# Adafruit_NeoPixel_JST_SH_Breakout.net
KiCad netlist of a schematic drawn in EAGLE
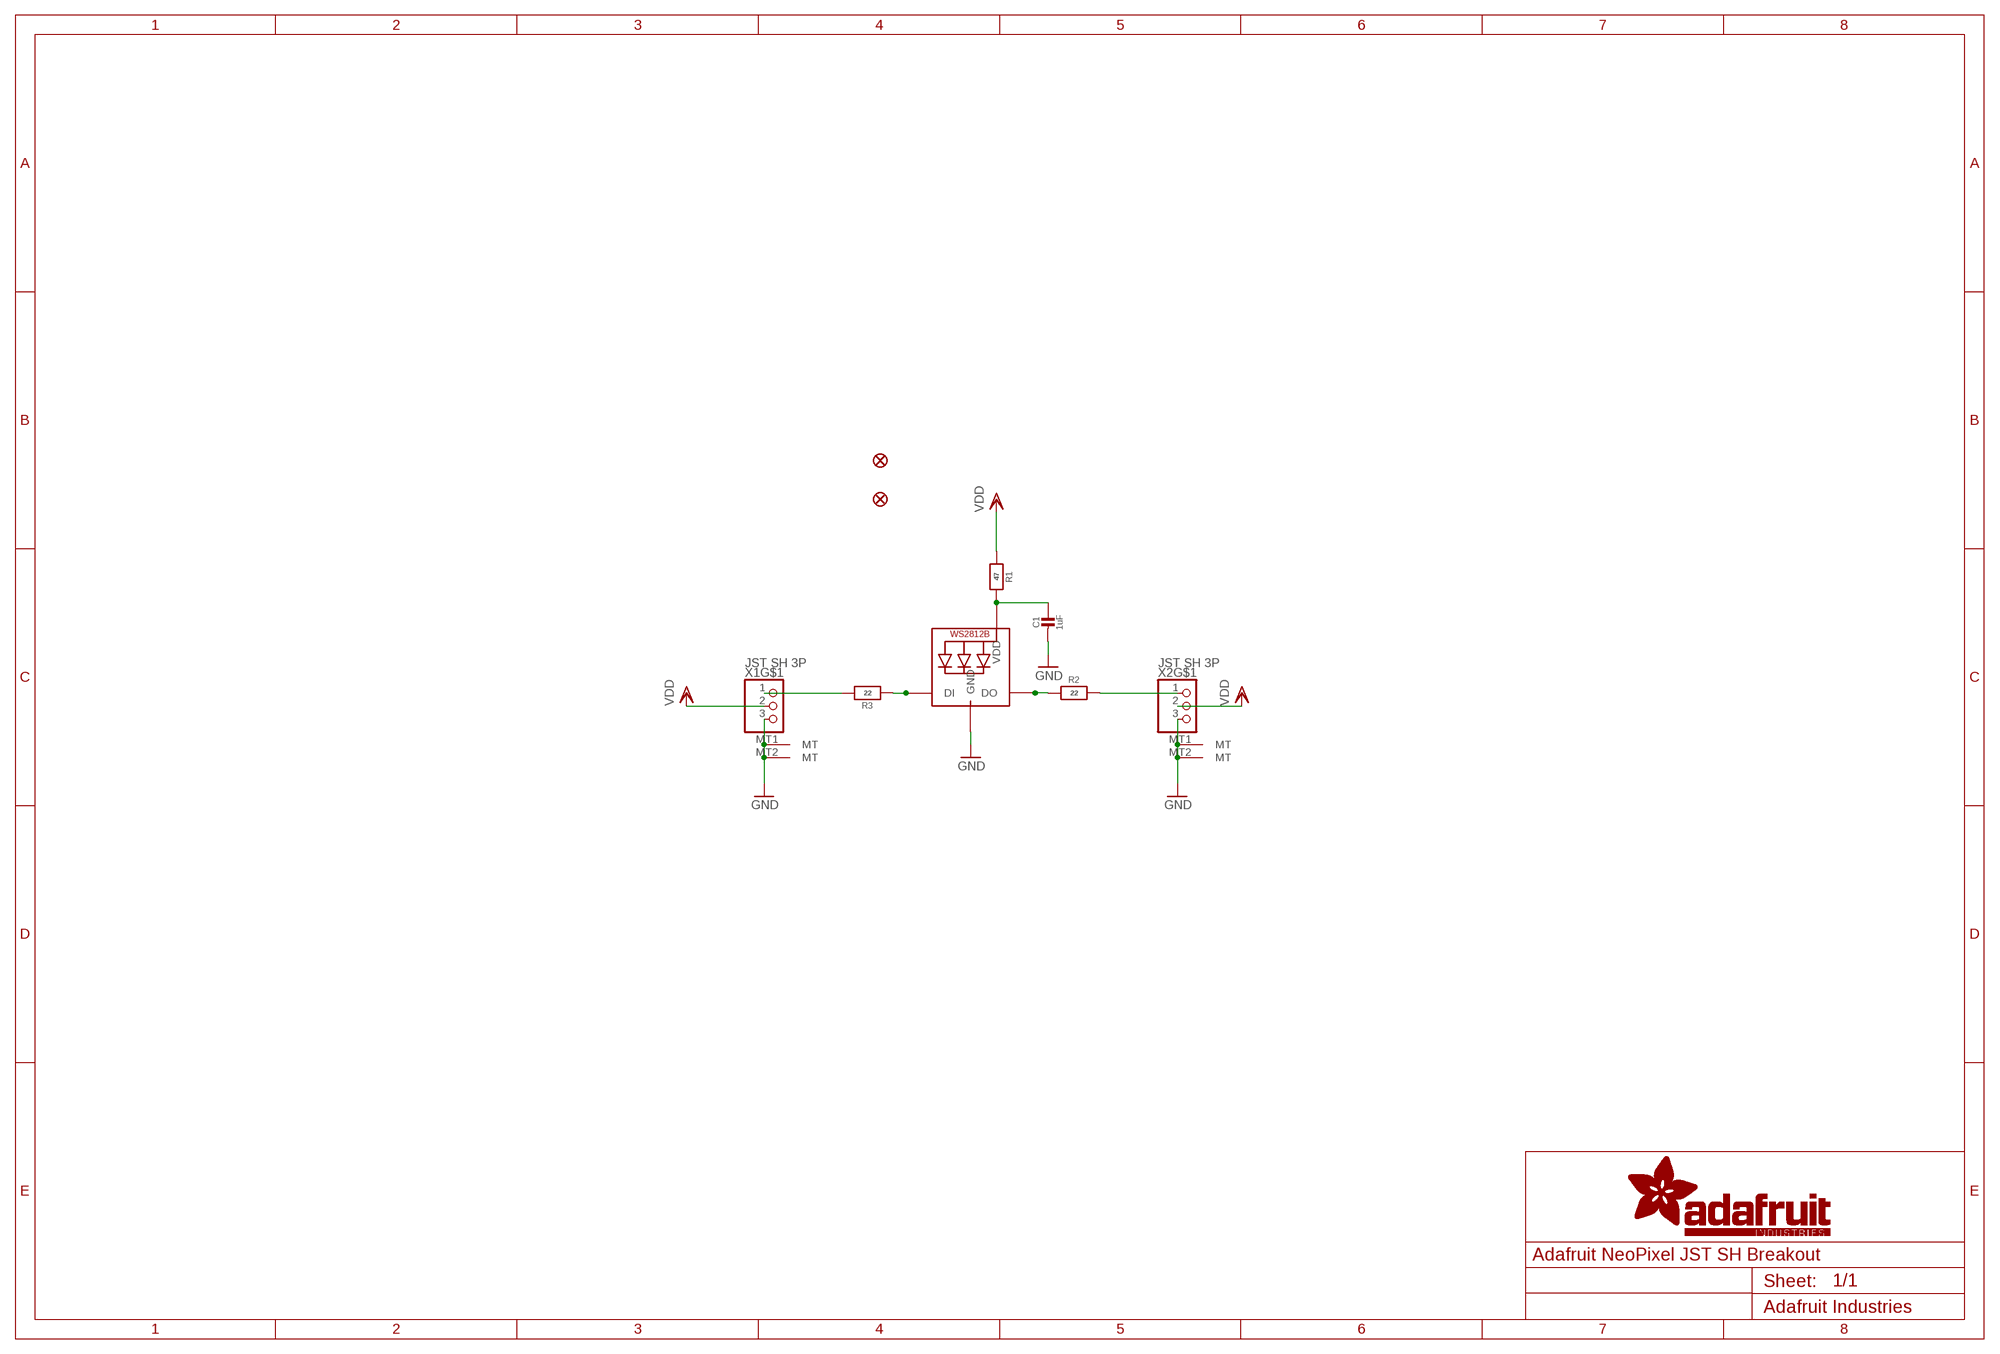
[diagram p0: schematic, sheet 1]

(export (version "E")
  (design (tool "Eeschema 10.0.6"))
  (components
    (comp (ref "C1")
      (value "1uF")
      (footprint "eagle-import:0603-NO")
      (libsource (lib "eagle-import") (part "CAP_CERAMIC0603_NO"))
    )
    (comp (ref "FID1")
      (value "FIDUCIAL_0.5MM")
      (footprint "eagle-import:FIDUCIAL_0.5MM")
      (libsource (lib "eagle-import") (part "FIDUCIAL_0.5MM"))
    )
    (comp (ref "FID2")
      (value "FIDUCIAL_0.5MM")
      (footprint "eagle-import:FIDUCIAL_0.5MM")
      (libsource (lib "eagle-import") (part "FIDUCIAL_0.5MM"))
    )
    (comp (ref "LED2")
      (value "WS2812B_5050N")
      (footprint "eagle-import:WS2812B-NARROW")
      (libsource (lib "eagle-import") (part "WS2812B_5050N"))
    )
    (comp (ref "R1")
      (value "47")
      (footprint "eagle-import:_0402NO")
      (libsource (lib "eagle-import") (part "RESISTOR_0402NO"))
    )
    (comp (ref "R2")
      (value "22")
      (footprint "eagle-import:_0402NO")
      (libsource (lib "eagle-import") (part "RESISTOR_0402NO"))
    )
    (comp (ref "R3")
      (value "22")
      (footprint "eagle-import:_0402NO")
      (libsource (lib "eagle-import") (part "RESISTOR_0402NO"))
    )
    (comp (ref "X1")
      (value "JST SH 3P")
      (footprint "eagle-import:JST_SH3")
      (libsource (lib "eagle-import") (part "CON_JST_SH_3PINHORZ"))
    )
    (comp (ref "X2")
      (value "JST SH 3P")
      (footprint "eagle-import:JST_SH3")
      (libsource (lib "eagle-import") (part "CON_JST_SH_3PINHORZ"))
    )
  )
  (nets
    (net (code "1") (name "GND") (class "Default")
      (node (ref "C1") (pin "2") (pinfunction "2_2") (pintype "passive"))
      (node (ref "LED2") (pin "3-GND") (pinfunction "GND_3-GND") (pintype "power_in"))
      (node (ref "X1") (pin "3") (pinfunction "3_3") (pintype "passive"))
      (node (ref "X1") (pin "MT1") (pinfunction "MT_MT1") (pintype "bidirectional"))
      (node (ref "X1") (pin "MT2") (pinfunction "MT_MT2") (pintype "bidirectional"))
      (node (ref "X2") (pin "3") (pinfunction "3_3") (pintype "passive"))
      (node (ref "X2") (pin "MT1") (pinfunction "MT_MT1") (pintype "bidirectional"))
      (node (ref "X2") (pin "MT2") (pinfunction "MT_MT2") (pintype "bidirectional"))
    )
    (net (code "2") (name "Net-(LED2-DI)") (class "Default")
      (node (ref "LED2") (pin "4-DIN") (pinfunction "DI_4-DIN") (pintype "input"))
      (node (ref "R3") (pin "1") (pinfunction "1_1") (pintype "passive"))
    )
    (net (code "3") (name "Net-(LED2-DO)") (class "Default")
      (node (ref "LED2") (pin "2-DOUT") (pinfunction "DO_2-DOUT") (pintype "output"))
      (node (ref "R2") (pin "1") (pinfunction "1_1") (pintype "passive"))
    )
    (net (code "4") (name "Net-(LED2-VDD)") (class "Default")
      (node (ref "C1") (pin "1") (pinfunction "1_1") (pintype "passive"))
      (node (ref "LED2") (pin "1-VDD") (pinfunction "VDD_1-VDD") (pintype "power_in"))
      (node (ref "R1") (pin "2") (pinfunction "2_2") (pintype "passive"))
    )
    (net (code "5") (name "Net-(R2-Pad2)") (class "Default")
      (node (ref "R2") (pin "2") (pinfunction "2_2") (pintype "passive"))
      (node (ref "X2") (pin "1") (pinfunction "1_1") (pintype "passive"))
    )
    (net (code "6") (name "Net-(R3-Pad2)") (class "Default")
      (node (ref "R3") (pin "2") (pinfunction "2_2") (pintype "passive"))
      (node (ref "X1") (pin "1") (pinfunction "1_1") (pintype "passive"))
    )
    (net (code "7") (name "VDD") (class "Default")
      (node (ref "R1") (pin "1") (pinfunction "1_1") (pintype "passive"))
      (node (ref "X1") (pin "2") (pinfunction "2_2") (pintype "passive"))
      (node (ref "X2") (pin "2") (pinfunction "2_2") (pintype "passive"))
    )
  )
)
